# untitled.net
KiCad netlist of a schematic drawn in EAGLE
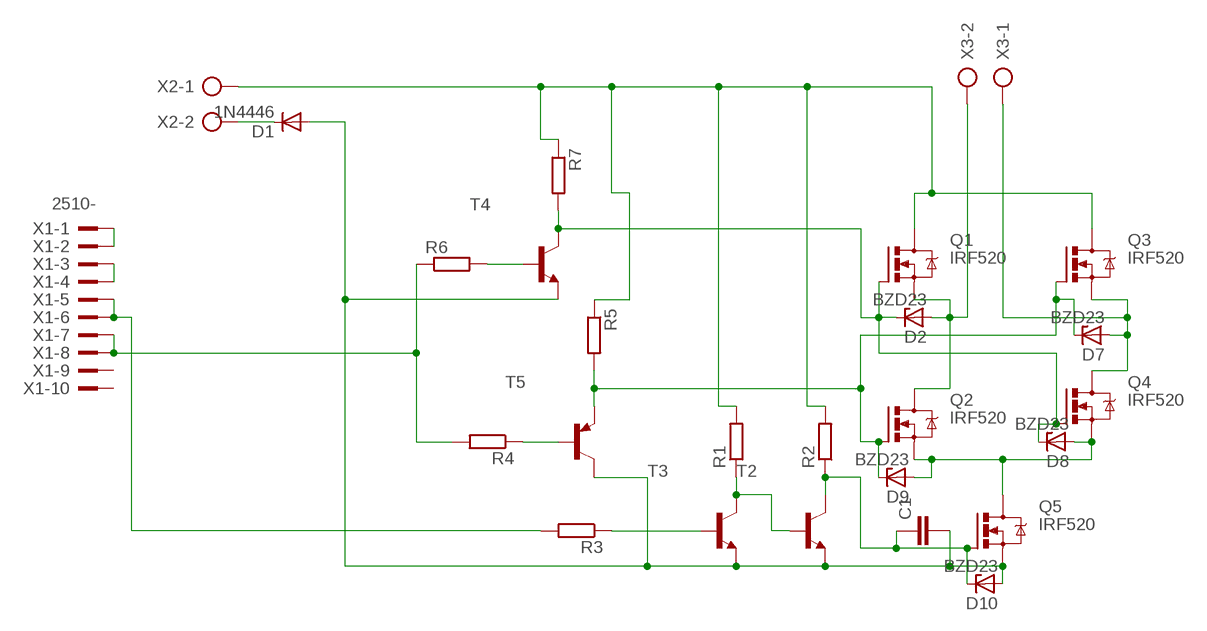
[diagram p0: schematic, sheet 1]

(export (version "E")
  (design (tool "Eeschema 10.0.6"))
  (components
    (comp (ref "C1")
      (value "C5/2.5")
      (footprint "eagle-import:C5B2.5")
      (libsource (lib "eagle-import") (part "C5/2.5"))
    )
    (comp (ref "D1")
      (value "1N4446")
      (footprint "eagle-import:DO35-10")
      (libsource (lib "eagle-import") (part "1N4446"))
    )
    (comp (ref "D2")
      (value "BZD23")
      (footprint "eagle-import:SOD81")
      (libsource (lib "eagle-import") (part "BZD23"))
    )
    (comp (ref "D7")
      (value "BZD23")
      (footprint "eagle-import:SOD81")
      (libsource (lib "eagle-import") (part "BZD23"))
    )
    (comp (ref "D8")
      (value "BZD23")
      (footprint "eagle-import:SOD81")
      (libsource (lib "eagle-import") (part "BZD23"))
    )
    (comp (ref "D9")
      (value "BZD23")
      (footprint "eagle-import:SOD81")
      (libsource (lib "eagle-import") (part "BZD23"))
    )
    (comp (ref "D10")
      (value "BZD23")
      (footprint "eagle-import:SOD81")
      (libsource (lib "eagle-import") (part "BZD23"))
    )
    (comp (ref "Q1")
      (value "IRF520")
      (footprint "eagle-import:TO220BV")
      (libsource (lib "eagle-import") (part "IRF520"))
    )
    (comp (ref "Q2")
      (value "IRF520")
      (footprint "eagle-import:TO220BV")
      (libsource (lib "eagle-import") (part "IRF520"))
    )
    (comp (ref "Q3")
      (value "IRF520")
      (footprint "eagle-import:TO220BV")
      (libsource (lib "eagle-import") (part "IRF520"))
    )
    (comp (ref "Q4")
      (value "IRF520")
      (footprint "eagle-import:TO220BV")
      (libsource (lib "eagle-import") (part "IRF520"))
    )
    (comp (ref "Q5")
      (value "IRF520")
      (footprint "eagle-import:TO220BV")
      (libsource (lib "eagle-import") (part "IRF520"))
    )
    (comp (ref "R1")
      (value "R-EU_0207/10")
      (footprint "eagle-import:0207_10")
      (libsource (lib "eagle-import") (part "R-EU_0207/10"))
    )
    (comp (ref "R2")
      (value "R-EU_0207/10")
      (footprint "eagle-import:0207_10")
      (libsource (lib "eagle-import") (part "R-EU_0207/10"))
    )
    (comp (ref "R3")
      (value "R-EU_0207/10")
      (footprint "eagle-import:0207_10")
      (libsource (lib "eagle-import") (part "R-EU_0207/10"))
    )
    (comp (ref "R4")
      (value "R-EU_0207/10")
      (footprint "eagle-import:0207_10")
      (libsource (lib "eagle-import") (part "R-EU_0207/10"))
    )
    (comp (ref "R5")
      (value "R-EU_0207/10")
      (footprint "eagle-import:0207_10")
      (libsource (lib "eagle-import") (part "R-EU_0207/10"))
    )
    (comp (ref "R6")
      (value "R-EU_0207/10")
      (footprint "eagle-import:0207_10")
      (libsource (lib "eagle-import") (part "R-EU_0207/10"))
    )
    (comp (ref "R7")
      (value "R-EU_0207/10")
      (footprint "eagle-import:0207_10")
      (libsource (lib "eagle-import") (part "R-EU_0207/10"))
    )
    (comp (ref "T2")
      (value "2N4124-NPN-TO92-CBE")
      (footprint "eagle-import:TO92-CBE")
      (libsource (lib "eagle-import") (part "-NPN-TO92-CBE2N4124"))
    )
    (comp (ref "T3")
      (value "2N4124-NPN-TO92-CBE")
      (footprint "eagle-import:TO92-CBE")
      (libsource (lib "eagle-import") (part "-NPN-TO92-CBE2N4124"))
    )
    (comp (ref "T4")
      (value "2N4124-NPN-TO92-CBE")
      (footprint "eagle-import:TO92-CBE")
      (libsource (lib "eagle-import") (part "-NPN-TO92-CBE2N4124"))
    )
    (comp (ref "T5")
      (value "BF493S-PNP-TO92-CBE")
      (footprint "eagle-import:TO92-CBE")
      (libsource (lib "eagle-import") (part "-PNP-TO92-CBEBF493S"))
    )
    (comp (ref "X1")
      (value "2510-")
      (footprint "eagle-import:PAK100_2500-10")
      (libsource (lib "eagle-import") (part "2510-"))
    )
    (comp (ref "X2")
      (value "AK300/2")
      (footprint "eagle-import:AK300_2")
      (libsource (lib "eagle-import") (part "AK300/2"))
    )
    (comp (ref "X3")
      (value "AK300/2")
      (footprint "eagle-import:AK300_2")
      (libsource (lib "eagle-import") (part "AK300/2"))
    )
  )
  (nets
    (net (code "1") (name "Net-(C1-Pad1)") (class "Default")
      (node (ref "C1") (pin "1") (pinfunction "1_1") (pintype "passive"))
      (node (ref "D10") (pin "C") (pinfunction "C_C") (pintype "passive"))
      (node (ref "Q5") (pin "G") (pinfunction "G_G") (pintype "passive"))
      (node (ref "R2") (pin "1") (pinfunction "1_1") (pintype "passive"))
      (node (ref "T2") (pin "C") (pinfunction "C_C") (pintype "passive"))
    )
    (net (code "2") (name "Net-(C1-Pad2)") (class "Default")
      (node (ref "C1") (pin "2") (pinfunction "2_2") (pintype "passive"))
      (node (ref "D1") (pin "A") (pinfunction "A_A") (pintype "passive"))
      (node (ref "D10") (pin "A") (pinfunction "A_A") (pintype "passive"))
      (node (ref "Q5") (pin "S") (pinfunction "S_S") (pintype "passive"))
      (node (ref "T2") (pin "E") (pinfunction "E_E") (pintype "passive"))
      (node (ref "T3") (pin "E") (pinfunction "E_E") (pintype "passive"))
      (node (ref "T4") (pin "E") (pinfunction "E_E") (pintype "passive"))
      (node (ref "T5") (pin "C") (pinfunction "C_C") (pintype "passive"))
    )
    (net (code "3") (name "Net-(D2-PadC)") (class "Default")
      (node (ref "D2") (pin "C") (pinfunction "C_C") (pintype "passive"))
      (node (ref "D8") (pin "C") (pinfunction "C_C") (pintype "passive"))
      (node (ref "Q1") (pin "G") (pinfunction "G_G") (pintype "passive"))
      (node (ref "Q4") (pin "G") (pinfunction "G_G") (pintype "passive"))
      (node (ref "R7") (pin "2") (pinfunction "2_2") (pintype "passive"))
      (node (ref "T4") (pin "C") (pinfunction "C_C") (pintype "passive"))
    )
    (net (code "4") (name "Net-(D7-PadC)") (class "Default")
      (node (ref "D7") (pin "C") (pinfunction "C_C") (pintype "passive"))
      (node (ref "D9") (pin "C") (pinfunction "C_C") (pintype "passive"))
      (node (ref "Q2") (pin "G") (pinfunction "G_G") (pintype "passive"))
      (node (ref "Q3") (pin "G") (pinfunction "G_G") (pintype "passive"))
      (node (ref "R5") (pin "2") (pinfunction "2_2") (pintype "passive"))
      (node (ref "T5") (pin "E") (pinfunction "E_E") (pintype "passive"))
    )
    (net (code "5") (name "Net-(D8-PadA)") (class "Default")
      (node (ref "D8") (pin "A") (pinfunction "A_A") (pintype "passive"))
      (node (ref "D9") (pin "A") (pinfunction "A_A") (pintype "passive"))
      (node (ref "Q2") (pin "S") (pinfunction "S_S") (pintype "passive"))
      (node (ref "Q4") (pin "S") (pinfunction "S_S") (pintype "passive"))
      (node (ref "Q5") (pin "D") (pinfunction "D_D") (pintype "passive"))
    )
    (net (code "6") (name "Net-(R1-Pad1)") (class "Default")
      (node (ref "R1") (pin "1") (pinfunction "1_1") (pintype "passive"))
      (node (ref "T2") (pin "B") (pinfunction "B_B") (pintype "passive"))
      (node (ref "T3") (pin "C") (pinfunction "C_C") (pintype "passive"))
    )
    (net (code "7") (name "Net-(R3-Pad1)") (class "Default")
      (node (ref "R3") (pin "1") (pinfunction "1_1") (pintype "passive"))
      (node (ref "T3") (pin "B") (pinfunction "B_B") (pintype "passive"))
    )
    (net (code "8") (name "Net-(R4-Pad1)") (class "Default")
      (node (ref "R4") (pin "1") (pinfunction "1_1") (pintype "passive"))
      (node (ref "T5") (pin "B") (pinfunction "B_B") (pintype "passive"))
    )
    (net (code "9") (name "Net-(R6-Pad2)") (class "Default")
      (node (ref "R6") (pin "2") (pinfunction "2_2") (pintype "passive"))
      (node (ref "T4") (pin "B") (pinfunction "B_B") (pintype "passive"))
    )
    (net (code "10") (name "Net-(X1A-KL)") (class "Default")
      (node (ref "X1") (pin "1") (pinfunction "KL_1") (pintype "passive"))
      (node (ref "X1") (pin "2") (pinfunction "KL_2") (pintype "passive"))
    )
    (net (code "11") (name "Net-(X1D-KL)") (class "Default")
      (node (ref "X1") (pin "3") (pinfunction "KL_3") (pintype "passive"))
      (node (ref "X1") (pin "4") (pinfunction "KL_4") (pintype "passive"))
    )
    (net (code "12") (name "Net-(X1F-KL)") (class "Default")
      (node (ref "R3") (pin "2") (pinfunction "2_2") (pintype "passive"))
      (node (ref "X1") (pin "5") (pinfunction "KL_5") (pintype "passive"))
      (node (ref "X1") (pin "6") (pinfunction "KL_6") (pintype "passive"))
    )
    (net (code "13") (name "Net-(X1H-KL)") (class "Default")
      (node (ref "R4") (pin "2") (pinfunction "2_2") (pintype "passive"))
      (node (ref "R6") (pin "1") (pinfunction "1_1") (pintype "passive"))
      (node (ref "X1") (pin "7") (pinfunction "KL_7") (pintype "passive"))
      (node (ref "X1") (pin "8") (pinfunction "KL_8") (pintype "passive"))
    )
    (net (code "14") (name "Net-(X2A-KL)") (class "Default")
      (node (ref "Q1") (pin "D") (pinfunction "D_D") (pintype "passive"))
      (node (ref "Q3") (pin "D") (pinfunction "D_D") (pintype "passive"))
      (node (ref "R1") (pin "2") (pinfunction "2_2") (pintype "passive"))
      (node (ref "R2") (pin "2") (pinfunction "2_2") (pintype "passive"))
      (node (ref "R5") (pin "1") (pinfunction "1_1") (pintype "passive"))
      (node (ref "R7") (pin "1") (pinfunction "1_1") (pintype "passive"))
      (node (ref "X2") (pin "1") (pinfunction "KL_1") (pintype "passive"))
    )
    (net (code "15") (name "Net-(X2B-KL)") (class "Default")
      (node (ref "D1") (pin "C") (pinfunction "C_C") (pintype "passive"))
      (node (ref "X2") (pin "2") (pinfunction "KL_2") (pintype "passive"))
    )
    (net (code "16") (name "Net-(X3A-KL)") (class "Default")
      (node (ref "D7") (pin "A") (pinfunction "A_A") (pintype "passive"))
      (node (ref "Q3") (pin "S") (pinfunction "S_S") (pintype "passive"))
      (node (ref "Q4") (pin "D") (pinfunction "D_D") (pintype "passive"))
      (node (ref "X3") (pin "1") (pinfunction "KL_1") (pintype "passive"))
    )
    (net (code "17") (name "Net-(X3B-KL)") (class "Default")
      (node (ref "D2") (pin "A") (pinfunction "A_A") (pintype "passive"))
      (node (ref "Q1") (pin "S") (pinfunction "S_S") (pintype "passive"))
      (node (ref "Q2") (pin "D") (pinfunction "D_D") (pintype "passive"))
      (node (ref "X3") (pin "2") (pinfunction "KL_2") (pintype "passive"))
    )
    (net (code "18") (name "unconnected-(X1B-KL-Pad10)") (class "Default")
      (node (ref "X1") (pin "10") (pinfunction "KL_10") (pintype "passive"))
    )
    (net (code "19") (name "unconnected-(X1J-KL-Pad9)") (class "Default")
      (node (ref "X1") (pin "9") (pinfunction "KL_9") (pintype "passive"))
    )
  )
)
